# Schematic_Eagle.net
KiCad netlist of a schematic drawn in EAGLE
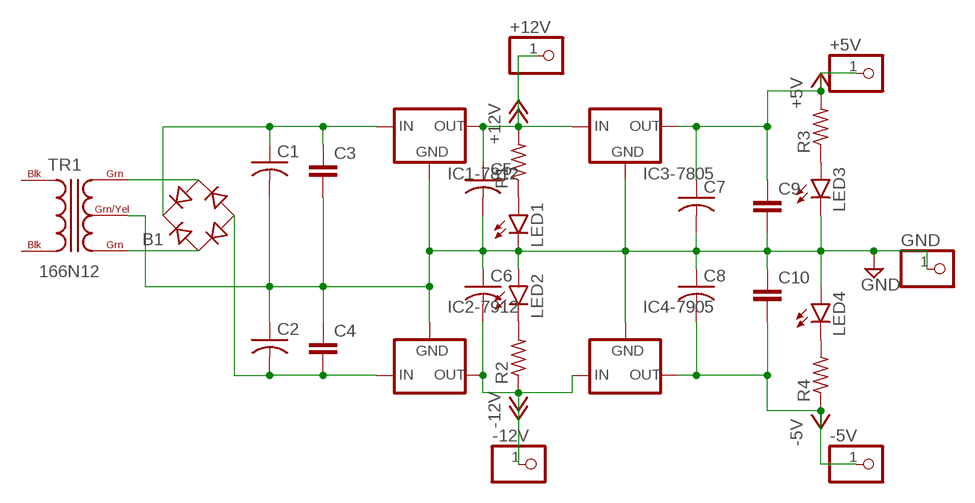
[diagram p0: schematic, sheet 1]

(export (version "E")
  (design (tool "Eeschema 10.0.6"))
  (components
    (comp (ref "+5V")
      (value "PINHD-1X1")
      (footprint "eagle-import:1X01")
      (libsource (lib "eagle-import") (part "PINHD-1X1"))
    )
    (comp (ref "+12V")
      (value "PINHD-1X1")
      (footprint "eagle-import:1X01")
      (libsource (lib "eagle-import") (part "PINHD-1X1"))
    )
    (comp (ref "-5V")
      (value "PINHD-1X1")
      (footprint "eagle-import:1X01")
      (libsource (lib "eagle-import") (part "PINHD-1X1"))
    )
    (comp (ref "-12V")
      (value "PINHD-1X1")
      (footprint "eagle-import:1X01")
      (libsource (lib "eagle-import") (part "PINHD-1X1"))
    )
    (comp (ref "B1")
      (value "RB1A")
      (footprint "eagle-import:RB1A")
      (libsource (lib "eagle-import") (part "RB1A"))
    )
    (comp (ref "C1")
      (value "C-US025-025X050")
      (footprint "eagle-import:C025-025X050")
      (libsource (lib "eagle-import") (part "C-US025-025X050"))
    )
    (comp (ref "C2")
      (value "C-US025-025X050")
      (footprint "eagle-import:C025-025X050")
      (libsource (lib "eagle-import") (part "C-US025-025X050"))
    )
    (comp (ref "C3")
      (value "C-EU025-025X050")
      (footprint "eagle-import:C025-025X050")
      (libsource (lib "eagle-import") (part "C-EU025-025X050"))
    )
    (comp (ref "C4")
      (value "C-EU025-025X050")
      (footprint "eagle-import:C025-025X050")
      (libsource (lib "eagle-import") (part "C-EU025-025X050"))
    )
    (comp (ref "C5")
      (value "C-US025-025X050")
      (footprint "eagle-import:C025-025X050")
      (libsource (lib "eagle-import") (part "C-US025-025X050"))
    )
    (comp (ref "C6")
      (value "C-US025-025X050")
      (footprint "eagle-import:C025-025X050")
      (libsource (lib "eagle-import") (part "C-US025-025X050"))
    )
    (comp (ref "C7")
      (value "C-US025-025X050")
      (footprint "eagle-import:C025-025X050")
      (libsource (lib "eagle-import") (part "C-US025-025X050"))
    )
    (comp (ref "C8")
      (value "C-US025-025X050")
      (footprint "eagle-import:C025-025X050")
      (libsource (lib "eagle-import") (part "C-US025-025X050"))
    )
    (comp (ref "C9")
      (value "C-EU025-025X050")
      (footprint "eagle-import:C025-025X050")
      (libsource (lib "eagle-import") (part "C-EU025-025X050"))
    )
    (comp (ref "C10")
      (value "C-EU025-025X050")
      (footprint "eagle-import:C025-025X050")
      (libsource (lib "eagle-import") (part "C-EU025-025X050"))
    )
    (comp (ref "GND")
      (value "PINHD-1X1")
      (footprint "eagle-import:1X01")
      (libsource (lib "eagle-import") (part "PINHD-1X1"))
    )
    (comp (ref "IC1-7812")
      (value "78XXL")
      (footprint "eagle-import:78XXL")
      (libsource (lib "eagle-import") (part "78XXL"))
    )
    (comp (ref "IC2-7912")
      (value "79XXL")
      (footprint "eagle-import:79XXL")
      (libsource (lib "eagle-import") (part "79XXL"))
    )
    (comp (ref "IC3-7805")
      (value "78XXL")
      (footprint "eagle-import:78XXL")
      (libsource (lib "eagle-import") (part "78XXL"))
    )
    (comp (ref "IC4-7905")
      (value "79XXL")
      (footprint "eagle-import:79XXL")
      (libsource (lib "eagle-import") (part "79XXL"))
    )
    (comp (ref "LED1")
      (value "LED5MM")
      (footprint "eagle-import:LED5MM")
      (libsource (lib "eagle-import") (part "LED5MM"))
    )
    (comp (ref "LED2")
      (value "LED5MM")
      (footprint "eagle-import:LED5MM")
      (libsource (lib "eagle-import") (part "LED5MM"))
    )
    (comp (ref "LED3")
      (value "LED5MM")
      (footprint "eagle-import:LED5MM")
      (libsource (lib "eagle-import") (part "LED5MM"))
    )
    (comp (ref "LED4")
      (value "LED5MM")
      (footprint "eagle-import:LED5MM")
      (libsource (lib "eagle-import") (part "LED5MM"))
    )
    (comp (ref "R1")
      (value "R-US_0204/7")
      (footprint "eagle-import:0204_7")
      (libsource (lib "eagle-import") (part "R-US_0204/7"))
    )
    (comp (ref "R2")
      (value "R-US_0204/7")
      (footprint "eagle-import:0204_7")
      (libsource (lib "eagle-import") (part "R-US_0204/7"))
    )
    (comp (ref "R3")
      (value "R-US_0204/7")
      (footprint "eagle-import:0204_7")
      (libsource (lib "eagle-import") (part "R-US_0204/7"))
    )
    (comp (ref "R4")
      (value "R-US_0204/7")
      (footprint "eagle-import:0204_7")
      (libsource (lib "eagle-import") (part "R-US_0204/7"))
    )
    (comp (ref "TR1")
      (value "166N12")
      (footprint "eagle-import:C13H")
      (libsource (lib "eagle-import") (part "166N12"))
    )
  )
  (nets
    (net (code "1") (name "+5V") (class "Default")
      (node (ref "+5V") (pin "1") (pinfunction "1_1") (pintype "passive"))
      (node (ref "C7") (pin "1") (pinfunction "1_1") (pintype "passive"))
      (node (ref "C9") (pin "1") (pinfunction "1_1") (pintype "passive"))
      (node (ref "IC3-7805") (pin "OUT") (pinfunction "OUT_OUT") (pintype "passive"))
      (node (ref "R3") (pin "2") (pinfunction "2_2") (pintype "passive"))
    )
    (net (code "2") (name "+12V") (class "Default")
      (node (ref "+12V") (pin "1") (pinfunction "1_1") (pintype "passive"))
      (node (ref "C5") (pin "1") (pinfunction "1_1") (pintype "passive"))
      (node (ref "IC1-7812") (pin "OUT") (pinfunction "OUT_OUT") (pintype "passive"))
      (node (ref "IC3-7805") (pin "IN") (pinfunction "IN_IN") (pintype "input"))
      (node (ref "R1") (pin "2") (pinfunction "2_2") (pintype "passive"))
    )
    (net (code "3") (name "-5V") (class "Default")
      (node (ref "-5V") (pin "1") (pinfunction "1_1") (pintype "passive"))
      (node (ref "C10") (pin "2") (pinfunction "2_2") (pintype "passive"))
      (node (ref "C8") (pin "2") (pinfunction "2_2") (pintype "passive"))
      (node (ref "IC4-7905") (pin "OUT") (pinfunction "OUT_OUT") (pintype "passive"))
      (node (ref "R4") (pin "1") (pinfunction "1_1") (pintype "passive"))
    )
    (net (code "4") (name "-12V") (class "Default")
      (node (ref "-12V") (pin "1") (pinfunction "1_1") (pintype "passive"))
      (node (ref "C6") (pin "2") (pinfunction "2_2") (pintype "passive"))
      (node (ref "IC2-7912") (pin "OUT") (pinfunction "OUT_OUT") (pintype "passive"))
      (node (ref "IC4-7905") (pin "IN") (pinfunction "IN_IN") (pintype "input"))
      (node (ref "R2") (pin "1") (pinfunction "1_1") (pintype "passive"))
    )
    (net (code "5") (name "GND") (class "Default")
      (node (ref "C1") (pin "2") (pinfunction "2_2") (pintype "passive"))
      (node (ref "C10") (pin "1") (pinfunction "1_1") (pintype "passive"))
      (node (ref "C2") (pin "1") (pinfunction "1_1") (pintype "passive"))
      (node (ref "C3") (pin "2") (pinfunction "2_2") (pintype "passive"))
      (node (ref "C4") (pin "1") (pinfunction "1_1") (pintype "passive"))
      (node (ref "C5") (pin "2") (pinfunction "2_2") (pintype "passive"))
      (node (ref "C6") (pin "1") (pinfunction "1_1") (pintype "passive"))
      (node (ref "C7") (pin "2") (pinfunction "2_2") (pintype "passive"))
      (node (ref "C8") (pin "1") (pinfunction "1_1") (pintype "passive"))
      (node (ref "C9") (pin "2") (pinfunction "2_2") (pintype "passive"))
      (node (ref "GND") (pin "1") (pinfunction "1_1") (pintype "passive"))
      (node (ref "IC1-7812") (pin "GND") (pinfunction "GND_GND") (pintype "input"))
      (node (ref "IC2-7912") (pin "GND") (pinfunction "GND_GND") (pintype "input"))
      (node (ref "IC3-7805") (pin "GND") (pinfunction "GND_GND") (pintype "input"))
      (node (ref "IC4-7905") (pin "GND") (pinfunction "GND_GND") (pintype "input"))
      (node (ref "LED1") (pin "K") (pinfunction "C_K") (pintype "passive"))
      (node (ref "LED2") (pin "A") (pinfunction "A_A") (pintype "passive"))
      (node (ref "LED3") (pin "K") (pinfunction "C_K") (pintype "passive"))
      (node (ref "LED4") (pin "A") (pinfunction "A_A") (pintype "passive"))
      (node (ref "TR1") (pin "GRN/YEL") (pinfunction "GRN/YEL_GRN/YEL") (pintype "passive"))
    )
    (net (code "6") (name "Net-(B1-Pad+)") (class "Default")
      (node (ref "B1") (pin "+") (pinfunction "+_+") (pintype "passive"))
      (node (ref "C1") (pin "1") (pinfunction "1_1") (pintype "passive"))
      (node (ref "C3") (pin "1") (pinfunction "1_1") (pintype "passive"))
      (node (ref "IC1-7812") (pin "IN") (pinfunction "IN_IN") (pintype "input"))
    )
    (net (code "7") (name "Net-(B1-Pad-)") (class "Default")
      (node (ref "B1") (pin "-") (pinfunction "-_-") (pintype "passive"))
      (node (ref "C2") (pin "2") (pinfunction "2_2") (pintype "passive"))
      (node (ref "C4") (pin "2") (pinfunction "2_2") (pintype "passive"))
      (node (ref "IC2-7912") (pin "IN") (pinfunction "IN_IN") (pintype "input"))
    )
    (net (code "8") (name "Net-(B1-PadAC1)") (class "Default")
      (node (ref "B1") (pin "AC1") (pinfunction "AC1_AC1") (pintype "passive"))
      (node (ref "TR1") (pin "GRN@2") (pinfunction "GRN_GRN@2") (pintype "passive"))
    )
    (net (code "9") (name "Net-(B1-PadAC2)") (class "Default")
      (node (ref "B1") (pin "AC2") (pinfunction "AC2_AC2") (pintype "passive"))
      (node (ref "TR1") (pin "GRN@1") (pinfunction "GRN_GRN@1") (pintype "passive"))
    )
    (net (code "10") (name "Net-(LED1-PadA)") (class "Default")
      (node (ref "LED1") (pin "A") (pinfunction "A_A") (pintype "passive"))
      (node (ref "R1") (pin "1") (pinfunction "1_1") (pintype "passive"))
    )
    (net (code "11") (name "Net-(LED2-C)") (class "Default")
      (node (ref "LED2") (pin "K") (pinfunction "C_K") (pintype "passive"))
      (node (ref "R2") (pin "2") (pinfunction "2_2") (pintype "passive"))
    )
    (net (code "12") (name "Net-(LED3-PadA)") (class "Default")
      (node (ref "LED3") (pin "A") (pinfunction "A_A") (pintype "passive"))
      (node (ref "R3") (pin "1") (pinfunction "1_1") (pintype "passive"))
    )
    (net (code "13") (name "Net-(LED4-C)") (class "Default")
      (node (ref "LED4") (pin "K") (pinfunction "C_K") (pintype "passive"))
      (node (ref "R4") (pin "2") (pinfunction "2_2") (pintype "passive"))
    )
    (net (code "14") (name "unconnected-(TR1-BLK-PadBLK@1)") (class "Default")
      (node (ref "TR1") (pin "BLK@1") (pinfunction "BLK_BLK@1") (pintype "passive"))
    )
    (net (code "15") (name "unconnected-(TR1-BLK-PadBLK@2)") (class "Default")
      (node (ref "TR1") (pin "BLK@2") (pinfunction "BLK_BLK@2") (pintype "passive"))
    )
  )
)
